# test-aetzen.net
KiCad netlist of a schematic drawn in EAGLE
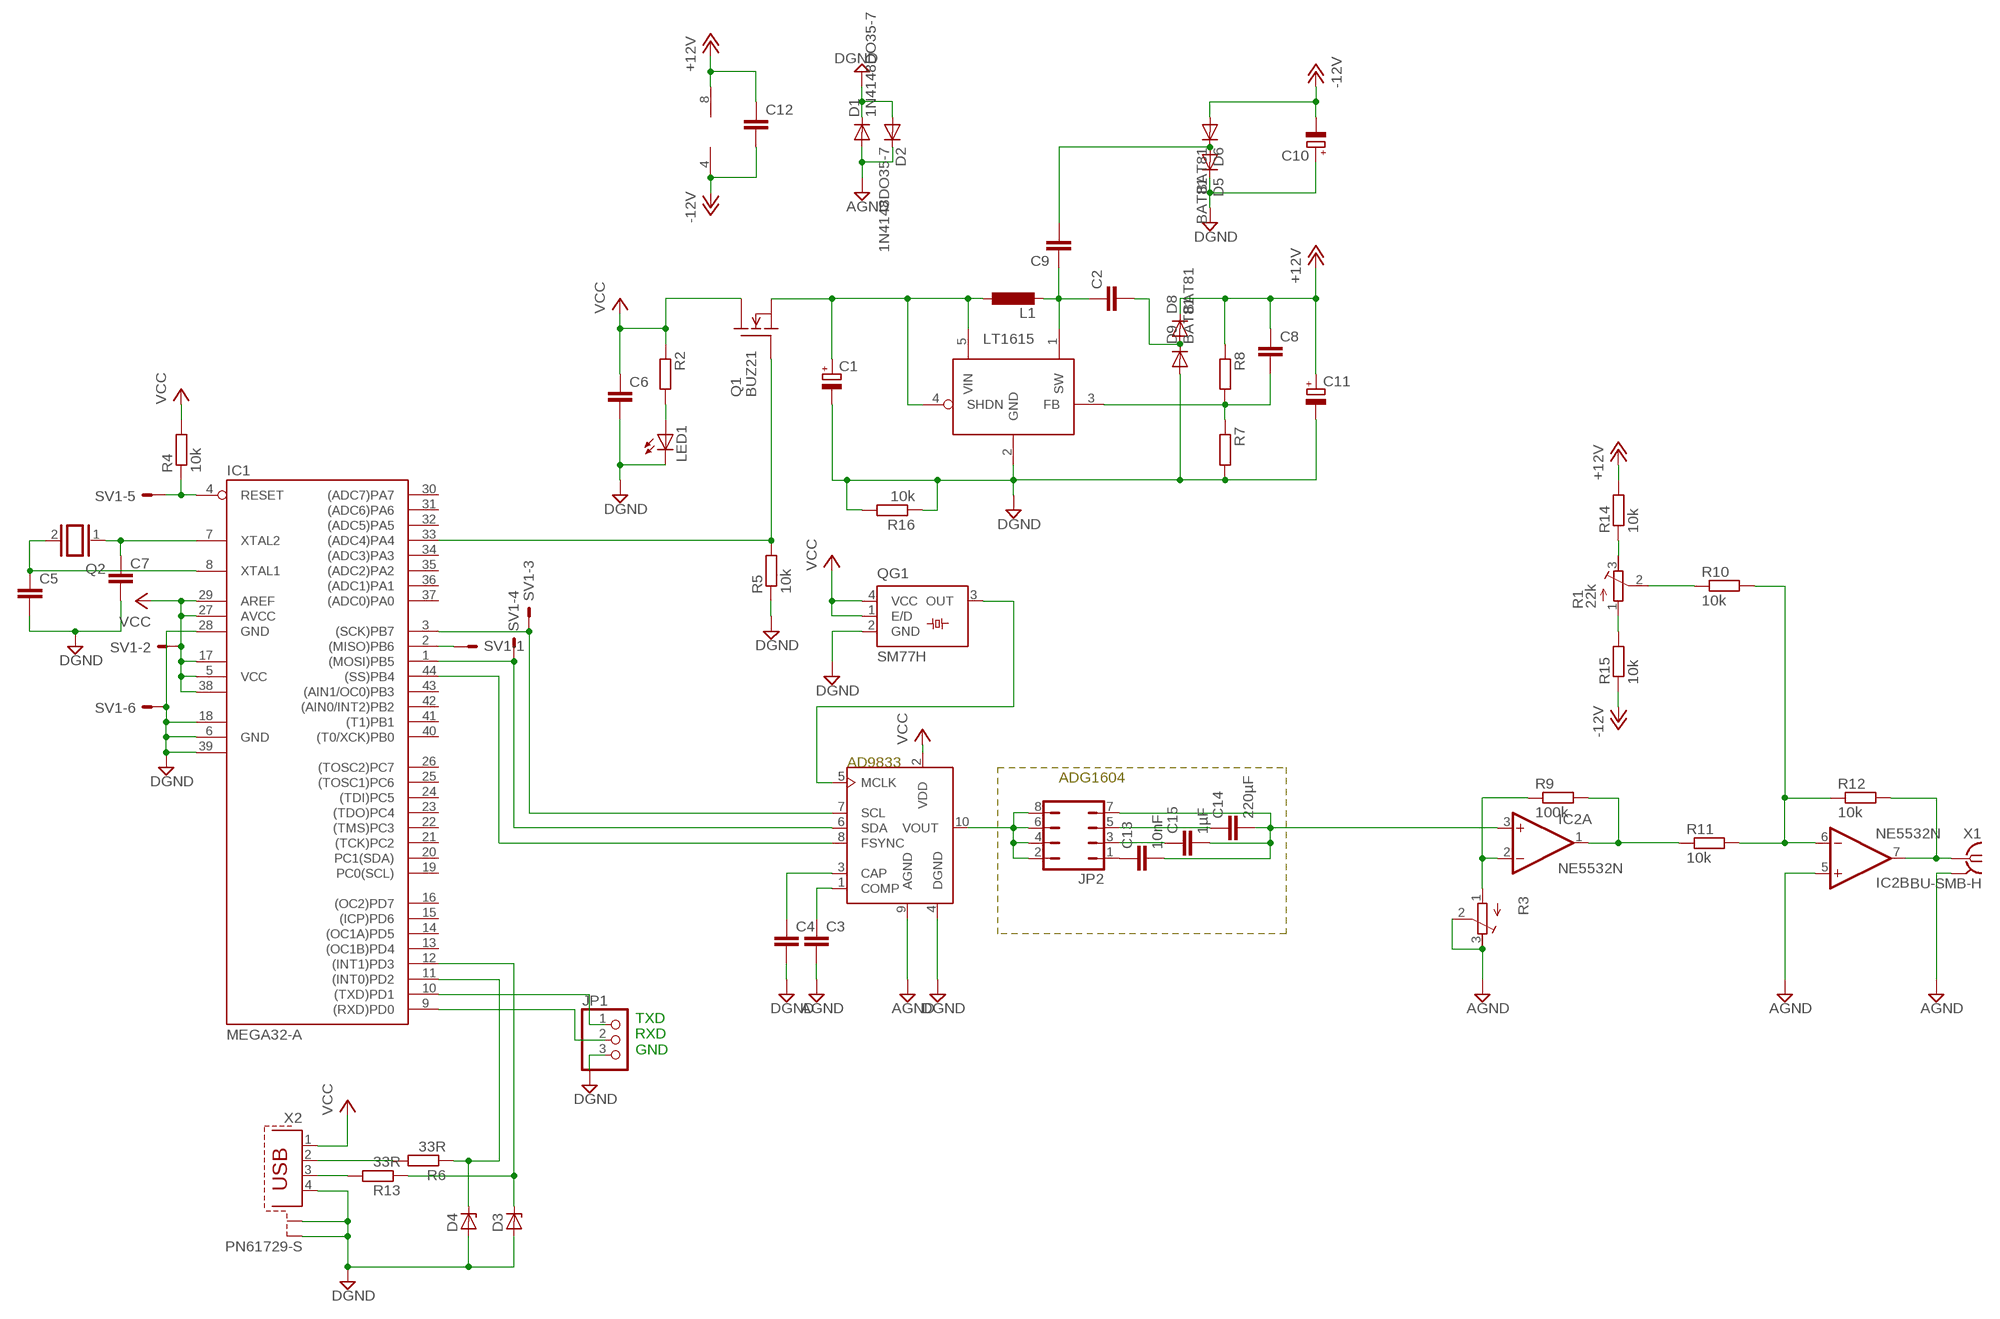
[diagram p0: schematic, sheet 1]

(export (version "E")
  (design (tool "Eeschema 10.0.6"))
  (components
    (comp (ref "C1")
      (value "CPOL-EUE3.5-8")
      (footprint "eagle-import:E3,5-8")
      (libsource (lib "eagle-import") (part "CPOL-EUE3.5-8"))
    )
    (comp (ref "C2")
      (value "C-EU025-024X044")
      (footprint "eagle-import:C025-024X044")
      (libsource (lib "eagle-import") (part "C-EU025-024X044"))
    )
    (comp (ref "C3")
      (value "C-EU025-024X044")
      (footprint "eagle-import:C025-024X044")
      (libsource (lib "eagle-import") (part "C-EU025-024X044"))
    )
    (comp (ref "C4")
      (value "C-EU025-024X044")
      (footprint "eagle-import:C025-024X044")
      (libsource (lib "eagle-import") (part "C-EU025-024X044"))
    )
    (comp (ref "C5")
      (value "C-EU025-024X044")
      (footprint "eagle-import:C025-024X044")
      (libsource (lib "eagle-import") (part "C-EU025-024X044"))
    )
    (comp (ref "C6")
      (value "C-EU025-024X044")
      (footprint "eagle-import:C025-024X044")
      (libsource (lib "eagle-import") (part "C-EU025-024X044"))
    )
    (comp (ref "C7")
      (value "C-EU025-024X044")
      (footprint "eagle-import:C025-024X044")
      (libsource (lib "eagle-import") (part "C-EU025-024X044"))
    )
    (comp (ref "C8")
      (value "C-EU025-024X044")
      (footprint "eagle-import:C025-024X044")
      (libsource (lib "eagle-import") (part "C-EU025-024X044"))
    )
    (comp (ref "C9")
      (value "C-EU025-024X044")
      (footprint "eagle-import:C025-024X044")
      (libsource (lib "eagle-import") (part "C-EU025-024X044"))
    )
    (comp (ref "C10")
      (value "CPOL-EUE3.5-8")
      (footprint "eagle-import:E3,5-8")
      (libsource (lib "eagle-import") (part "CPOL-EUE3.5-8"))
    )
    (comp (ref "C11")
      (value "CPOL-EUE3.5-8")
      (footprint "eagle-import:E3,5-8")
      (libsource (lib "eagle-import") (part "CPOL-EUE3.5-8"))
    )
    (comp (ref "C12")
      (value "C-EU025-024X044")
      (footprint "eagle-import:C025-024X044")
      (libsource (lib "eagle-import") (part "C-EU025-024X044"))
    )
    (comp (ref "C13")
      (value "10nF")
      (footprint "eagle-import:C025-024X044")
      (libsource (lib "eagle-import") (part "C-EU025-024X044"))
    )
    (comp (ref "C14")
      (value "220µF")
      (footprint "eagle-import:C025-024X044")
      (libsource (lib "eagle-import") (part "C-EU025-024X044"))
    )
    (comp (ref "C15")
      (value "1µF")
      (footprint "eagle-import:C025-024X044")
      (libsource (lib "eagle-import") (part "C-EU025-024X044"))
    )
    (comp (ref "D1")
      (value "1N4148DO35-7")
      (footprint "eagle-import:DO35-7")
      (libsource (lib "eagle-import") (part "1N4148DO35-7"))
    )
    (comp (ref "D2")
      (value "1N4148DO35-7")
      (footprint "eagle-import:DO35-7")
      (libsource (lib "eagle-import") (part "1N4148DO35-7"))
    )
    (comp (ref "D3")
      (value "ZENER-DIODEDO35Z10")
      (footprint "eagle-import:DO35Z10")
      (libsource (lib "eagle-import") (part "ZENER-DIODEDO35Z10"))
    )
    (comp (ref "D4")
      (value "ZENER-DIODEDO35Z10")
      (footprint "eagle-import:DO35Z10")
      (libsource (lib "eagle-import") (part "ZENER-DIODEDO35Z10"))
    )
    (comp (ref "D5")
      (value "BAT81")
      (footprint "eagle-import:DO34-7")
      (libsource (lib "eagle-import") (part "BAT81"))
    )
    (comp (ref "D6")
      (value "BAT81")
      (footprint "eagle-import:DO34-7")
      (libsource (lib "eagle-import") (part "BAT81"))
    )
    (comp (ref "D8")
      (value "BAT81")
      (footprint "eagle-import:DO34-7")
      (libsource (lib "eagle-import") (part "BAT81"))
    )
    (comp (ref "D9")
      (value "BAT81")
      (footprint "eagle-import:DO34-7")
      (libsource (lib "eagle-import") (part "BAT81"))
    )
    (comp (ref "IC1")
      (value "MEGA32-A")
      (footprint "eagle-import:TQFP44")
      (fields (field (name "MPN") "ATMEGA32-16AU"))
      (libsource (lib "eagle-import") (part "MEGA32-A"))
    )
    (comp (ref "IC2")
      (value "NE5532N")
      (footprint "eagle-import:DIL08")
      (libsource (lib "eagle-import") (part "NE5532N"))
    )
    (comp (ref "JP1")
      (value "PINHD-1X3")
      (footprint "eagle-import:1X03")
      (libsource (lib "eagle-import") (part "PINHD-1X3"))
    )
    (comp (ref "JP2")
      (value "JP4Q")
      (footprint "eagle-import:JP4Q")
      (libsource (lib "eagle-import") (part "JP4Q"))
    )
    (comp (ref "L1")
      (value "L-EU0207/10")
      (footprint "eagle-import:0207_10")
      (libsource (lib "eagle-import") (part "L-EU0207/10"))
    )
    (comp (ref "LED1")
      (value "LED5MM")
      (footprint "eagle-import:LED5MM")
      (libsource (lib "eagle-import") (part "LED5MM"))
    )
    (comp (ref "Q1")
      (value "BUZ21")
      (footprint "eagle-import:TO220V")
      (libsource (lib "eagle-import") (part "BUZ21"))
    )
    (comp (ref "Q2")
      (value "XTAL/S")
      (footprint "eagle-import:QS")
      (libsource (lib "eagle-import") (part "XTAL/S"))
    )
    (comp (ref "QG1")
      (value "SM77H")
      (footprint "eagle-import:SM77H")
      (libsource (lib "eagle-import") (part "SM77H"))
    )
    (comp (ref "R1")
      (value "22k")
      (footprint "eagle-import:RTRIM64Y")
      (libsource (lib "eagle-import") (part "R-TRIMM64Y"))
    )
    (comp (ref "R2")
      (value "R-EU_0207/10")
      (footprint "eagle-import:0207_10")
      (libsource (lib "eagle-import") (part "R-EU_0207/10"))
    )
    (comp (ref "R3")
      (value "R-TRIMM64Y")
      (footprint "eagle-import:RTRIM64Y")
      (libsource (lib "eagle-import") (part "R-TRIMM64Y"))
    )
    (comp (ref "R4")
      (value "10k")
      (footprint "eagle-import:M1206")
      (libsource (lib "eagle-import") (part "R-EU_M1206"))
    )
    (comp (ref "R5")
      (value "10k")
      (footprint "eagle-import:M1206")
      (libsource (lib "eagle-import") (part "R-EU_M1206"))
    )
    (comp (ref "R6")
      (value "33R")
      (footprint "eagle-import:0207_10")
      (libsource (lib "eagle-import") (part "R-EU_0207/10"))
    )
    (comp (ref "R7")
      (value "R-EU_0207/10")
      (footprint "eagle-import:0207_10")
      (libsource (lib "eagle-import") (part "R-EU_0207/10"))
    )
    (comp (ref "R8")
      (value "R-EU_0207/10")
      (footprint "eagle-import:0207_10")
      (libsource (lib "eagle-import") (part "R-EU_0207/10"))
    )
    (comp (ref "R9")
      (value "100k")
      (footprint "eagle-import:0207_10")
      (libsource (lib "eagle-import") (part "R-EU_0207/10"))
    )
    (comp (ref "R10")
      (value "10k")
      (footprint "eagle-import:M1206")
      (libsource (lib "eagle-import") (part "R-EU_M1206"))
    )
    (comp (ref "R11")
      (value "10k")
      (footprint "eagle-import:M1206")
      (libsource (lib "eagle-import") (part "R-EU_M1206"))
    )
    (comp (ref "R12")
      (value "10k")
      (footprint "eagle-import:M1206")
      (libsource (lib "eagle-import") (part "R-EU_M1206"))
    )
    (comp (ref "R13")
      (value "33R")
      (footprint "eagle-import:0207_10")
      (libsource (lib "eagle-import") (part "R-EU_0207/10"))
    )
    (comp (ref "R14")
      (value "10k")
      (footprint "eagle-import:M1206")
      (libsource (lib "eagle-import") (part "R-EU_M1206"))
    )
    (comp (ref "R15")
      (value "10k")
      (footprint "eagle-import:M1206")
      (libsource (lib "eagle-import") (part "R-EU_M1206"))
    )
    (comp (ref "R16")
      (value "10k")
      (footprint "eagle-import:M1206")
      (libsource (lib "eagle-import") (part "R-EU_M1206"))
    )
    (comp (ref "SV1")
      (value "ML6E")
      (footprint "eagle-import:ML6")
      (libsource (lib "eagle-import") (part "ML6?E"))
    )
    (comp (ref "U$1")
      (value "AD9833-P")
      (footprint "eagle-import:DIL10")
      (libsource (lib "eagle-import") (part "AD9833-P"))
    )
    (comp (ref "U$2")
      (value "LT1615")
      (footprint "eagle-import:SOT23-5")
      (libsource (lib "eagle-import") (part "LT1615"))
    )
    (comp (ref "X1")
      (value "BU-SMB-H")
      (footprint "eagle-import:BU-SMB-H")
      (libsource (lib "eagle-import") (part "BU-SMB-H"))
    )
    (comp (ref "X2")
      (value "PN61729-S")
      (footprint "eagle-import:PN61729-S")
      (libsource (lib "eagle-import") (part "PN61729-S"))
    )
  )
  (nets
    (net (code "1") (name "+12V") (class "Default")
      (node (ref "C11") (pin "+") (pinfunction "+_+") (pintype "passive"))
      (node (ref "C12") (pin "1") (pinfunction "1_1") (pintype "passive"))
      (node (ref "C8") (pin "1") (pinfunction "1_1") (pintype "passive"))
      (node (ref "D8") (pin "C") (pinfunction "C_C") (pintype "passive"))
      (node (ref "IC2") (pin "8") (pinfunction "V+_8") (pintype "power_in"))
      (node (ref "R14") (pin "2") (pinfunction "2_2") (pintype "passive"))
      (node (ref "R8") (pin "1") (pinfunction "1_1") (pintype "passive"))
    )
    (net (code "2") (name "-12V") (class "Default")
      (node (ref "C10") (pin "-") (pinfunction "-_-") (pintype "passive"))
      (node (ref "C12") (pin "2") (pinfunction "2_2") (pintype "passive"))
      (node (ref "D6") (pin "A") (pinfunction "A_A") (pintype "passive"))
      (node (ref "IC2") (pin "4") (pinfunction "V-_4") (pintype "power_in"))
      (node (ref "R15") (pin "1") (pinfunction "1_1") (pintype "passive"))
    )
    (net (code "3") (name "AGND") (class "Default")
      (node (ref "C3") (pin "2") (pinfunction "2_2") (pintype "passive"))
      (node (ref "D1") (pin "A") (pinfunction "A_A") (pintype "passive"))
      (node (ref "D2") (pin "C") (pinfunction "C_C") (pintype "passive"))
      (node (ref "IC2") (pin "5") (pinfunction "+IN_5") (pintype "input"))
      (node (ref "R3") (pin "2") (pinfunction "S_2") (pintype "passive"))
      (node (ref "R3") (pin "3") (pinfunction "E_3") (pintype "passive"))
      (node (ref "U$1") (pin "9") (pinfunction "AGND_9") (pintype "bidirectional"))
      (node (ref "X1") (pin "2") (pinfunction "2_2") (pintype "passive"))
      (node (ref "X1") (pin "3") (pinfunction "2_3") (pintype "passive"))
      (node (ref "X1") (pin "4") (pinfunction "2_4") (pintype "passive"))
      (node (ref "X1") (pin "5") (pinfunction "2_5") (pintype "passive"))
    )
    (net (code "4") (name "DGND") (class "Default")
      (node (ref "C1") (pin "-") (pinfunction "-_-") (pintype "passive"))
      (node (ref "C10") (pin "+") (pinfunction "+_+") (pintype "passive"))
      (node (ref "C11") (pin "-") (pinfunction "-_-") (pintype "passive"))
      (node (ref "C4") (pin "2") (pinfunction "2_2") (pintype "passive"))
      (node (ref "C5") (pin "2") (pinfunction "2_2") (pintype "passive"))
      (node (ref "C6") (pin "2") (pinfunction "2_2") (pintype "passive"))
      (node (ref "C7") (pin "2") (pinfunction "2_2") (pintype "passive"))
      (node (ref "D1") (pin "C") (pinfunction "C_C") (pintype "passive"))
      (node (ref "D2") (pin "A") (pinfunction "A_A") (pintype "passive"))
      (node (ref "D3") (pin "A") (pinfunction "A_A") (pintype "passive"))
      (node (ref "D4") (pin "A") (pinfunction "A_A") (pintype "passive"))
      (node (ref "D5") (pin "C") (pinfunction "C_C") (pintype "passive"))
      (node (ref "D9") (pin "A") (pinfunction "A_A") (pintype "passive"))
      (node (ref "IC1") (pin "18") (pinfunction "GND1_18") (pintype "power_in"))
      (node (ref "IC1") (pin "28") (pinfunction "GND_28") (pintype "power_in"))
      (node (ref "IC1") (pin "39") (pinfunction "GND2_39") (pintype "power_in"))
      (node (ref "IC1") (pin "6") (pinfunction "GND_6") (pintype "power_in"))
      (node (ref "JP1") (pin "3") (pinfunction "3_3") (pintype "passive"))
      (node (ref "LED1") (pin "K") (pinfunction "C_K") (pintype "passive"))
      (node (ref "QG1") (pin "2") (pinfunction "GND_2") (pintype "power_in"))
      (node (ref "R16") (pin "1") (pinfunction "1_1") (pintype "passive"))
      (node (ref "R16") (pin "2") (pinfunction "2_2") (pintype "passive"))
      (node (ref "R5") (pin "1") (pinfunction "1_1") (pintype "passive"))
      (node (ref "R7") (pin "2") (pinfunction "2_2") (pintype "passive"))
      (node (ref "SV1") (pin "6") (pinfunction "S_6") (pintype "passive"))
      (node (ref "U$1") (pin "4") (pinfunction "DGND_4") (pintype "bidirectional"))
      (node (ref "U$2") (pin "2") (pinfunction "GND_2") (pintype "bidirectional"))
      (node (ref "X2") (pin "4") (pinfunction "4_4") (pintype "passive"))
      (node (ref "X2") (pin "S1") (pinfunction "S1_S1") (pintype "passive"))
      (node (ref "X2") (pin "S2") (pinfunction "S2_S2") (pintype "passive"))
    )
    (net (code "5") (name "Net-(C2-Pad2)") (class "Default")
      (node (ref "C2") (pin "2") (pinfunction "2_2") (pintype "passive"))
      (node (ref "D8") (pin "A") (pinfunction "A_A") (pintype "passive"))
      (node (ref "D9") (pin "C") (pinfunction "C_C") (pintype "passive"))
    )
    (net (code "6") (name "Net-(C9-Pad2)") (class "Default")
      (node (ref "C9") (pin "2") (pinfunction "2_2") (pintype "passive"))
      (node (ref "D5") (pin "A") (pinfunction "A_A") (pintype "passive"))
      (node (ref "D6") (pin "C") (pinfunction "C_C") (pintype "passive"))
    )
    (net (code "7") (name "Net-(C13-Pad1)") (class "Default")
      (node (ref "C13") (pin "1") (pinfunction "1_1") (pintype "passive"))
      (node (ref "JP2") (pin "1") (pinfunction "1_1") (pintype "passive"))
    )
    (net (code "8") (name "Net-(C14-Pad1)") (class "Default")
      (node (ref "C14") (pin "1") (pinfunction "1_1") (pintype "passive"))
      (node (ref "JP2") (pin "5") (pinfunction "5_5") (pintype "passive"))
    )
    (net (code "9") (name "Net-(C15-Pad1)") (class "Default")
      (node (ref "C15") (pin "1") (pinfunction "1_1") (pintype "passive"))
      (node (ref "JP2") (pin "3") (pinfunction "3_3") (pintype "passive"))
    )
    (net (code "10") (name "Net-(IC1-(ADC4)PA4)") (class "Default")
      (node (ref "IC1") (pin "33") (pinfunction "(ADC4)PA4_33") (pintype "bidirectional"))
      (node (ref "Q1") (pin "1") (pinfunction "G_1") (pintype "passive"))
      (node (ref "R5") (pin "2") (pinfunction "2_2") (pintype "passive"))
    )
    (net (code "11") (name "Net-(IC1-(INT0)PD2)") (class "Default")
      (node (ref "D4") (pin "C") (pinfunction "C_C") (pintype "passive"))
      (node (ref "IC1") (pin "11") (pinfunction "(INT0)PD2_11") (pintype "bidirectional"))
      (node (ref "R6") (pin "1") (pinfunction "1_1") (pintype "passive"))
    )
    (net (code "12") (name "Net-(IC1-(INT1)PD3)") (class "Default")
      (node (ref "D3") (pin "C") (pinfunction "C_C") (pintype "passive"))
      (node (ref "IC1") (pin "12") (pinfunction "(INT1)PD3_12") (pintype "bidirectional"))
      (node (ref "R13") (pin "1") (pinfunction "1_1") (pintype "passive"))
    )
    (net (code "13") (name "Net-(IC1-(MISO)PB6)") (class "Default")
      (node (ref "IC1") (pin "2") (pinfunction "(MISO)PB6_2") (pintype "bidirectional"))
      (node (ref "SV1") (pin "1") (pinfunction "S_1") (pintype "passive"))
    )
    (net (code "14") (name "Net-(IC1-(MOSI)PB5)") (class "Default")
      (node (ref "IC1") (pin "1") (pinfunction "(MOSI)PB5_1") (pintype "bidirectional"))
      (node (ref "SV1") (pin "4") (pinfunction "S_4") (pintype "passive"))
      (node (ref "U$1") (pin "6") (pinfunction "SDA_6") (pintype "bidirectional"))
    )
    (net (code "15") (name "Net-(IC1-(RXD)PD0)") (class "Default")
      (node (ref "IC1") (pin "9") (pinfunction "(RXD)PD0_9") (pintype "bidirectional"))
      (node (ref "JP1") (pin "2") (pinfunction "2_2") (pintype "passive"))
    )
    (net (code "16") (name "Net-(IC1-(SCK)PB7)") (class "Default")
      (node (ref "IC1") (pin "3") (pinfunction "(SCK)PB7_3") (pintype "bidirectional"))
      (node (ref "SV1") (pin "3") (pinfunction "S_3") (pintype "passive"))
      (node (ref "U$1") (pin "7") (pinfunction "SCL_7") (pintype "bidirectional"))
    )
    (net (code "17") (name "Net-(IC1-(SS)PB4)") (class "Default")
      (node (ref "IC1") (pin "44") (pinfunction "(SS)PB4_44") (pintype "bidirectional"))
      (node (ref "U$1") (pin "8") (pinfunction "FSYNC_8") (pintype "bidirectional"))
    )
    (net (code "18") (name "Net-(IC1-(TXD)PD1)") (class "Default")
      (node (ref "IC1") (pin "10") (pinfunction "(TXD)PD1_10") (pintype "bidirectional"))
      (node (ref "JP1") (pin "1") (pinfunction "1_1") (pintype "passive"))
    )
    (net (code "19") (name "Net-(IC1-RESET)") (class "Default")
      (node (ref "IC1") (pin "4") (pinfunction "RESET_4") (pintype "input"))
      (node (ref "R4") (pin "1") (pinfunction "1_1") (pintype "passive"))
      (node (ref "SV1") (pin "5") (pinfunction "S_5") (pintype "passive"))
    )
    (net (code "20") (name "Net-(IC1-XTAL1)") (class "Default")
      (node (ref "C5") (pin "1") (pinfunction "1_1") (pintype "passive"))
      (node (ref "IC1") (pin "8") (pinfunction "XTAL1_8") (pintype "bidirectional"))
      (node (ref "Q2") (pin "2") (pinfunction "2_2") (pintype "passive"))
    )
    (net (code "21") (name "Net-(IC1-XTAL2)") (class "Default")
      (node (ref "C7") (pin "1") (pinfunction "1_1") (pintype "passive"))
      (node (ref "IC1") (pin "7") (pinfunction "XTAL2_7") (pintype "bidirectional"))
      (node (ref "Q2") (pin "1") (pinfunction "1_1") (pintype "passive"))
    )
    (net (code "22") (name "Net-(IC2A-+IN)") (class "Default")
      (node (ref "C13") (pin "2") (pinfunction "2_2") (pintype "passive"))
      (node (ref "C14") (pin "2") (pinfunction "2_2") (pintype "passive"))
      (node (ref "C15") (pin "2") (pinfunction "2_2") (pintype "passive"))
      (node (ref "IC2") (pin "3") (pinfunction "+IN_3") (pintype "input"))
      (node (ref "JP2") (pin "7") (pinfunction "7_7") (pintype "passive"))
    )
    (net (code "23") (name "Net-(IC2A--IN)") (class "Default")
      (node (ref "IC2") (pin "2") (pinfunction "-IN_2") (pintype "input"))
      (node (ref "R3") (pin "1") (pinfunction "A_1") (pintype "passive"))
      (node (ref "R9") (pin "1") (pinfunction "1_1") (pintype "passive"))
    )
    (net (code "24") (name "Net-(IC2A-OUT)") (class "Default")
      (node (ref "IC2") (pin "1") (pinfunction "OUT_1") (pintype "output"))
      (node (ref "R11") (pin "1") (pinfunction "1_1") (pintype "passive"))
      (node (ref "R9") (pin "2") (pinfunction "2_2") (pintype "passive"))
    )
    (net (code "25") (name "Net-(IC2B--IN)") (class "Default")
      (node (ref "IC2") (pin "6") (pinfunction "-IN_6") (pintype "input"))
      (node (ref "R10") (pin "2") (pinfunction "2_2") (pintype "passive"))
      (node (ref "R11") (pin "2") (pinfunction "2_2") (pintype "passive"))
      (node (ref "R12") (pin "1") (pinfunction "1_1") (pintype "passive"))
    )
    (net (code "26") (name "Net-(IC2B-OUT)") (class "Default")
      (node (ref "IC2") (pin "7") (pinfunction "OUT_7") (pintype "output"))
      (node (ref "R12") (pin "2") (pinfunction "2_2") (pintype "passive"))
      (node (ref "X1") (pin "1") (pinfunction "1_1") (pintype "passive"))
    )
    (net (code "27") (name "Net-(LED1-PadA)") (class "Default")
      (node (ref "LED1") (pin "A") (pinfunction "A_A") (pintype "passive"))
      (node (ref "R2") (pin "2") (pinfunction "2_2") (pintype "passive"))
    )
    (net (code "28") (name "Net-(Q1-S)") (class "Default")
      (node (ref "C1") (pin "+") (pinfunction "+_+") (pintype "passive"))
      (node (ref "L1") (pin "1") (pinfunction "1_1") (pintype "passive"))
      (node (ref "Q1") (pin "3") (pinfunction "S_3") (pintype "passive"))
      (node (ref "U$2") (pin "4") (pinfunction "SHDN_4") (pintype "bidirectional"))
      (node (ref "U$2") (pin "5") (pinfunction "VIN_5") (pintype "bidirectional"))
    )
    (net (code "29") (name "Net-(QG1-OUT)") (class "Default")
      (node (ref "QG1") (pin "3") (pinfunction "OUT_3") (pintype "output"))
      (node (ref "U$1") (pin "5") (pinfunction "MCLK_5") (pintype "bidirectional"))
    )
    (net (code "30") (name "Net-(R1-A)") (class "Default")
      (node (ref "R1") (pin "1") (pinfunction "A_1") (pintype "passive"))
      (node (ref "R15") (pin "2") (pinfunction "2_2") (pintype "passive"))
    )
    (net (code "31") (name "Net-(R1-E)") (class "Default")
      (node (ref "R1") (pin "3") (pinfunction "E_3") (pintype "passive"))
      (node (ref "R14") (pin "1") (pinfunction "1_1") (pintype "passive"))
    )
    (net (code "32") (name "Net-(R1-S)") (class "Default")
      (node (ref "R1") (pin "2") (pinfunction "S_2") (pintype "passive"))
      (node (ref "R10") (pin "1") (pinfunction "1_1") (pintype "passive"))
    )
    (net (code "33") (name "Net-(R6-Pad2)") (class "Default")
      (node (ref "R6") (pin "2") (pinfunction "2_2") (pintype "passive"))
      (node (ref "X2") (pin "2") (pinfunction "2_2") (pintype "passive"))
    )
    (net (code "34") (name "Net-(R13-Pad2)") (class "Default")
      (node (ref "R13") (pin "2") (pinfunction "2_2") (pintype "passive"))
      (node (ref "X2") (pin "3") (pinfunction "3_3") (pintype "passive"))
    )
    (net (code "35") (name "Net-(U$1-CAP)") (class "Default")
      (node (ref "C4") (pin "1") (pinfunction "1_1") (pintype "passive"))
      (node (ref "U$1") (pin "3") (pinfunction "CAP_3") (pintype "bidirectional"))
    )
    (net (code "36") (name "Net-(U$1-COMP)") (class "Default")
      (node (ref "C3") (pin "1") (pinfunction "1_1") (pintype "passive"))
      (node (ref "U$1") (pin "1") (pinfunction "COMP_1") (pintype "bidirectional"))
    )
    (net (code "37") (name "Net-(U$1-VOUT)") (class "Default")
      (node (ref "JP2") (pin "2") (pinfunction "2_2") (pintype "passive"))
      (node (ref "JP2") (pin "4") (pinfunction "4_4") (pintype "passive"))
      (node (ref "JP2") (pin "6") (pinfunction "6_6") (pintype "passive"))
      (node (ref "JP2") (pin "8") (pinfunction "8_8") (pintype "passive"))
      (node (ref "U$1") (pin "10") (pinfunction "VOUT_10") (pintype "bidirectional"))
    )
    (net (code "38") (name "Net-(U$2-FB)") (class "Default")
      (node (ref "C8") (pin "2") (pinfunction "2_2") (pintype "passive"))
      (node (ref "R7") (pin "1") (pinfunction "1_1") (pintype "passive"))
      (node (ref "R8") (pin "2") (pinfunction "2_2") (pintype "passive"))
      (node (ref "U$2") (pin "3") (pinfunction "FB_3") (pintype "bidirectional"))
    )
    (net (code "39") (name "Net-(U$2-SW)") (class "Default")
      (node (ref "C2") (pin "1") (pinfunction "1_1") (pintype "passive"))
      (node (ref "C9") (pin "1") (pinfunction "1_1") (pintype "passive"))
      (node (ref "L1") (pin "2") (pinfunction "2_2") (pintype "passive"))
      (node (ref "U$2") (pin "1") (pinfunction "SW_1") (pintype "bidirectional"))
    )
    (net (code "40") (name "VCC") (class "Default")
      (node (ref "C6") (pin "1") (pinfunction "1_1") (pintype "passive"))
      (node (ref "IC1") (pin "17") (pinfunction "VCC1_17") (pintype "power_in"))
      (node (ref "IC1") (pin "27") (pinfunction "AVCC_27") (pintype "power_in"))
      (node (ref "IC1") (pin "29") (pinfunction "AREF_29") (pintype "passive"))
      (node (ref "IC1") (pin "38") (pinfunction "VCC2_38") (pintype "power_in"))
      (node (ref "IC1") (pin "5") (pinfunction "VCC_5") (pintype "power_in"))
      (node (ref "Q1") (pin "2") (pinfunction "D_2") (pintype "passive"))
      (node (ref "QG1") (pin "1") (pinfunction "E/D_1") (pintype "input"))
      (node (ref "QG1") (pin "4") (pinfunction "VCC_4") (pintype "power_in"))
      (node (ref "R2") (pin "1") (pinfunction "1_1") (pintype "passive"))
      (node (ref "R4") (pin "2") (pinfunction "2_2") (pintype "passive"))
      (node (ref "SV1") (pin "2") (pinfunction "S_2") (pintype "passive"))
      (node (ref "U$1") (pin "2") (pinfunction "VDD_2") (pintype "bidirectional"))
      (node (ref "X2") (pin "1") (pinfunction "1_1") (pintype "passive"))
    )
    (net (code "41") (name "unconnected-(IC1-(ADC0)PA0-Pad37)") (class "Default")
      (node (ref "IC1") (pin "37") (pinfunction "(ADC0)PA0_37") (pintype "bidirectional"))
    )
    (net (code "42") (name "unconnected-(IC1-(ADC1)PA1-Pad36)") (class "Default")
      (node (ref "IC1") (pin "36") (pinfunction "(ADC1)PA1_36") (pintype "bidirectional"))
    )
    (net (code "43") (name "unconnected-(IC1-(ADC2)PA2-Pad35)") (class "Default")
      (node (ref "IC1") (pin "35") (pinfunction "(ADC2)PA2_35") (pintype "bidirectional"))
    )
    (net (code "44") (name "unconnected-(IC1-(ADC3)PA3-Pad34)") (class "Default")
      (node (ref "IC1") (pin "34") (pinfunction "(ADC3)PA3_34") (pintype "bidirectional"))
    )
    (net (code "45") (name "unconnected-(IC1-(ADC5)PA5-Pad32)") (class "Default")
      (node (ref "IC1") (pin "32") (pinfunction "(ADC5)PA5_32") (pintype "bidirectional"))
    )
    (net (code "46") (name "unconnected-(IC1-(ADC6)PA6-Pad31)") (class "Default")
      (node (ref "IC1") (pin "31") (pinfunction "(ADC6)PA6_31") (pintype "bidirectional"))
    )
    (net (code "47") (name "unconnected-(IC1-(ADC7)PA7-Pad30)") (class "Default")
      (node (ref "IC1") (pin "30") (pinfunction "(ADC7)PA7_30") (pintype "bidirectional"))
    )
    (net (code "48") (name "unconnected-(IC1-(AIN0{slash}INT2)PB2-Pad42)") (class "Default")
      (node (ref "IC1") (pin "42") (pinfunction "(AIN0/INT2)PB2_42") (pintype "bidirectional"))
    )
    (net (code "49") (name "unconnected-(IC1-(AIN1{slash}OC0)PB3-Pad43)") (class "Default")
      (node (ref "IC1") (pin "43") (pinfunction "(AIN1/OC0)PB3_43") (pintype "bidirectional"))
    )
    (net (code "50") (name "unconnected-(IC1-(ICP)PD6-Pad15)") (class "Default")
      (node (ref "IC1") (pin "15") (pinfunction "(ICP)PD6_15") (pintype "bidirectional"))
    )
    (net (code "51") (name "unconnected-(IC1-(OC1A)PD5-Pad14)") (class "Default")
      (node (ref "IC1") (pin "14") (pinfunction "(OC1A)PD5_14") (pintype "bidirectional"))
    )
    (net (code "52") (name "unconnected-(IC1-(OC1B)PD4-Pad13)") (class "Default")
      (node (ref "IC1") (pin "13") (pinfunction "(OC1B)PD4_13") (pintype "bidirectional"))
    )
    (net (code "53") (name "unconnected-(IC1-(OC2)PD7-Pad16)") (class "Default")
      (node (ref "IC1") (pin "16") (pinfunction "(OC2)PD7_16") (pintype "bidirectional"))
    )
    (net (code "54") (name "unconnected-(IC1-(T0{slash}XCK)PB0-Pad40)") (class "Default")
      (node (ref "IC1") (pin "40") (pinfunction "(T0/XCK)PB0_40") (pintype "bidirectional"))
    )
    (net (code "55") (name "unconnected-(IC1-(T1)PB1-Pad41)") (class "Default")
      (node (ref "IC1") (pin "41") (pinfunction "(T1)PB1_41") (pintype "bidirectional"))
    )
    (net (code "56") (name "unconnected-(IC1-(TCK)PC2-Pad21)") (class "Default")
      (node (ref "IC1") (pin "21") (pinfunction "(TCK)PC2_21") (pintype "bidirectional"))
    )
    (net (code "57") (name "unconnected-(IC1-(TDI)PC5-Pad24)") (class "Default")
      (node (ref "IC1") (pin "24") (pinfunction "(TDI)PC5_24") (pintype "bidirectional"))
    )
    (net (code "58") (name "unconnected-(IC1-(TDO)PC4-Pad23)") (class "Default")
      (node (ref "IC1") (pin "23") (pinfunction "(TDO)PC4_23") (pintype "bidirectional"))
    )
    (net (code "59") (name "unconnected-(IC1-(TMS)PC3-Pad22)") (class "Default")
      (node (ref "IC1") (pin "22") (pinfunction "(TMS)PC3_22") (pintype "bidirectional"))
    )
    (net (code "60") (name "unconnected-(IC1-(TOSC1)PC6-Pad25)") (class "Default")
      (node (ref "IC1") (pin "25") (pinfunction "(TOSC1)PC6_25") (pintype "bidirectional"))
    )
    (net (code "61") (name "unconnected-(IC1-(TOSC2)PC7-Pad26)") (class "Default")
      (node (ref "IC1") (pin "26") (pinfunction "(TOSC2)PC7_26") (pintype "bidirectional"))
    )
    (net (code "62") (name "unconnected-(IC1-PC0(SCL)-Pad19)") (class "Default")
      (node (ref "IC1") (pin "19") (pinfunction "PC0(SCL)_19") (pintype "bidirectional"))
    )
    (net (code "63") (name "unconnected-(IC1-PC1(SDA)-Pad20)") (class "Default")
      (node (ref "IC1") (pin "20") (pinfunction "PC1(SDA)_20") (pintype "bidirectional"))
    )
  )
)
